# electric_scheme.net
KiCad netlist of a schematic drawn in EAGLE
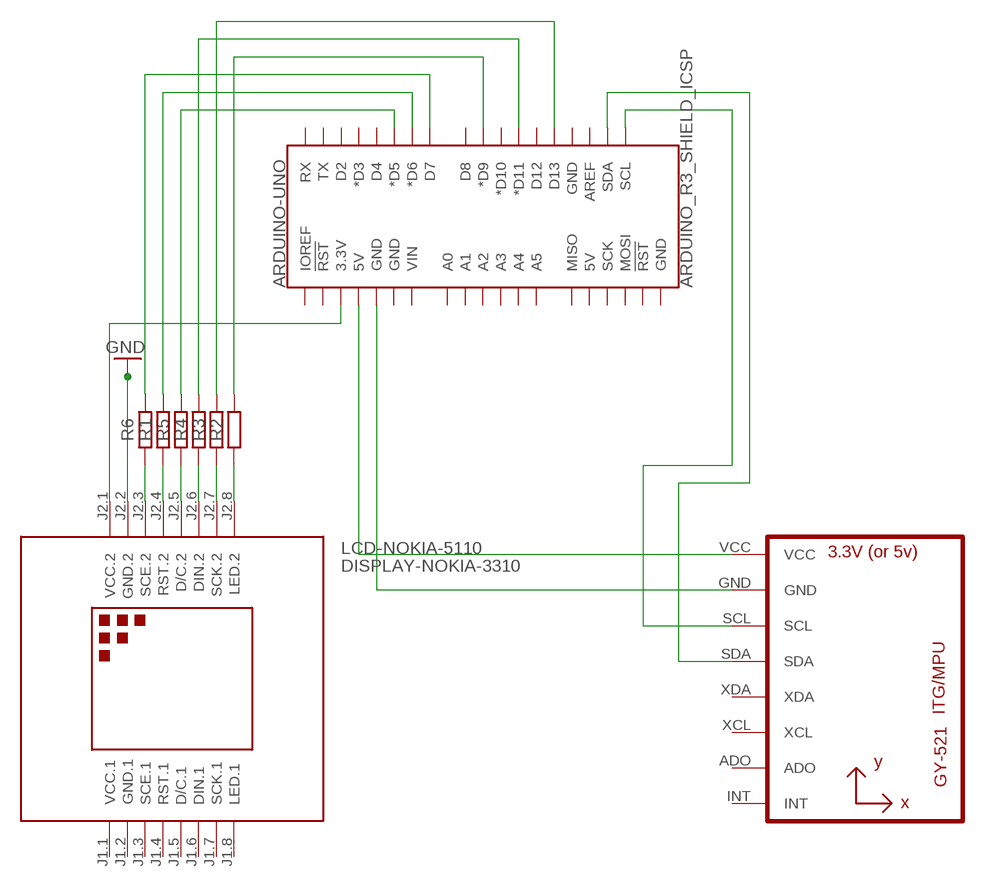
[diagram p0: schematic, sheet 1]

(export (version "E")
  (design (tool "Eeschema 10.0.6"))
  (components
    (comp (ref "ARDUINO-UNO")
      (value "ARDUINO_R3_SHIELD_ICSP")
      (footprint "eagle-import:UNO_R3_SHIELD_ICSP")
      (libsource (lib "eagle-import") (part "ARDUINO_R3_SHIELD_ICSP"))
    )
    (comp (ref "LCD-NOKIA-5110")
      (value "DISPLAY-NOKIA-3310")
      (footprint "eagle-import:DISPLAY-NOKIA-3310")
      (libsource (lib "eagle-import") (part "DISPLAY-NOKIA-3310"))
    )
    (comp (ref "MPU-6500")
      (value "GY-521MPU6050")
      (footprint "eagle-import:GY-521")
      (libsource (lib "eagle-import") (part "GY-521MPU6050"))
    )
    (comp (ref "R1")
      (value "R_AXIAL-11.7MM-PITCH")
      (footprint "eagle-import:RESAD1176W63L850D250B")
      (libsource (lib "eagle-import") (part "RAXIAL-11.7MM-PITCH_"))
    )
    (comp (ref "R2")
      (value "R_AXIAL-11.7MM-PITCH")
      (footprint "eagle-import:RESAD1176W63L850D250B")
      (libsource (lib "eagle-import") (part "RAXIAL-11.7MM-PITCH_"))
    )
    (comp (ref "R3")
      (value "R_AXIAL-11.7MM-PITCH")
      (footprint "eagle-import:RESAD1176W63L850D250B")
      (libsource (lib "eagle-import") (part "RAXIAL-11.7MM-PITCH_"))
    )
    (comp (ref "R4")
      (value "R_AXIAL-11.7MM-PITCH")
      (footprint "eagle-import:RESAD1176W63L850D250B")
      (libsource (lib "eagle-import") (part "RAXIAL-11.7MM-PITCH_"))
    )
    (comp (ref "R5")
      (value "R_AXIAL-11.7MM-PITCH")
      (footprint "eagle-import:RESAD1176W63L850D250B")
      (libsource (lib "eagle-import") (part "RAXIAL-11.7MM-PITCH_"))
    )
    (comp (ref "R6")
      (value "R_AXIAL-11.7MM-PITCH")
      (footprint "eagle-import:RESAD1176W63L850D250B")
      (libsource (lib "eagle-import") (part "RAXIAL-11.7MM-PITCH_"))
    )
  )
  (nets
    (net (code "1") (name "/GND.1") (class "Default")
      (node (ref "LCD-NOKIA-5110") (pin "J1.2") (pinfunction "GND.1_J1.2") (pintype "power_in"))
    )
    (net (code "2") (name "/VCC.1") (class "Default")
      (node (ref "LCD-NOKIA-5110") (pin "J1.1") (pinfunction "VCC.1_J1.1") (pintype "power_in"))
    )
    (net (code "3") (name "GND") (class "Default")
      (node (ref "LCD-NOKIA-5110") (pin "J2.2") (pinfunction "GND.2_J2.2") (pintype "power_in"))
    )
    (net (code "4") (name "Net-(ARDUINO-UNO-*D5)") (class "Default")
      (node (ref "ARDUINO-UNO") (pin "D5") (pinfunction "*D5_D5") (pintype "bidirectional"))
      (node (ref "R5") (pin "2") (pinfunction "2_2") (pintype "passive"))
    )
    (net (code "5") (name "Net-(ARDUINO-UNO-*D6)") (class "Default")
      (node (ref "ARDUINO-UNO") (pin "D6") (pinfunction "*D6_D6") (pintype "bidirectional"))
      (node (ref "R1") (pin "2") (pinfunction "2_2") (pintype "passive"))
    )
    (net (code "6") (name "Net-(ARDUINO-UNO-*D9)") (class "Default")
      (node (ref "ARDUINO-UNO") (pin "D9") (pinfunction "*D9_D9") (pintype "bidirectional"))
      (node (ref "R2") (pin "2") (pinfunction "2_2") (pintype "passive"))
    )
    (net (code "7") (name "Net-(ARDUINO-UNO-*D11)") (class "Default")
      (node (ref "ARDUINO-UNO") (pin "D11") (pinfunction "*D11_D11") (pintype "bidirectional"))
      (node (ref "R4") (pin "2") (pinfunction "2_2") (pintype "passive"))
    )
    (net (code "8") (name "Net-(ARDUINO-UNO-GND-PadGND@0)") (class "Default")
      (node (ref "ARDUINO-UNO") (pin "GND@0") (pinfunction "GND_GND@0") (pintype "bidirectional"))
      (node (ref "MPU-6500") (pin "GND") (pinfunction "GND_GND") (pintype "bidirectional"))
    )
    (net (code "9") (name "Net-(ARDUINO-UNO-Pad5V)") (class "Default")
      (node (ref "ARDUINO-UNO") (pin "5V") (pinfunction "5V_5V") (pintype "bidirectional"))
      (node (ref "MPU-6500") (pin "VCC") (pinfunction "VCC_VCC") (pintype "bidirectional"))
    )
    (net (code "10") (name "Net-(ARDUINO-UNO-PadD7)") (class "Default")
      (node (ref "ARDUINO-UNO") (pin "D7") (pinfunction "D7_D7") (pintype "bidirectional"))
      (node (ref "R6") (pin "2") (pinfunction "2_2") (pintype "passive"))
    )
    (net (code "11") (name "Net-(ARDUINO-UNO-PadD13)") (class "Default")
      (node (ref "ARDUINO-UNO") (pin "D13") (pinfunction "D13_D13") (pintype "bidirectional"))
      (node (ref "R3") (pin "2") (pinfunction "2_2") (pintype "passive"))
    )
    (net (code "12") (name "Net-(ARDUINO-UNO-PadSCL)") (class "Default")
      (node (ref "ARDUINO-UNO") (pin "SCL") (pinfunction "SCL_SCL") (pintype "bidirectional"))
      (node (ref "MPU-6500") (pin "SCL") (pinfunction "SCL_SCL") (pintype "bidirectional"))
    )
    (net (code "13") (name "Net-(ARDUINO-UNO-PadSDA)") (class "Default")
      (node (ref "ARDUINO-UNO") (pin "SDA") (pinfunction "SDA_SDA") (pintype "bidirectional"))
      (node (ref "MPU-6500") (pin "SDA") (pinfunction "SDA_SDA") (pintype "bidirectional"))
    )
    (net (code "14") (name "Net-(LCD-NOKIA-5110-DIN.2)") (class "Default")
      (node (ref "LCD-NOKIA-5110") (pin "J2.6") (pinfunction "DIN.2_J2.6") (pintype "bidirectional"))
      (node (ref "R4") (pin "1") (pinfunction "1_1") (pintype "passive"))
    )
    (net (code "15") (name "Net-(LCD-NOKIA-5110-D{slash}C.2)") (class "Default")
      (node (ref "LCD-NOKIA-5110") (pin "J2.5") (pinfunction "D/C.2_J2.5") (pintype "bidirectional"))
      (node (ref "R5") (pin "1") (pinfunction "1_1") (pintype "passive"))
    )
    (net (code "16") (name "Net-(LCD-NOKIA-5110-LED.2)") (class "Default")
      (node (ref "LCD-NOKIA-5110") (pin "J2.8") (pinfunction "LED.2_J2.8") (pintype "input"))
      (node (ref "R2") (pin "1") (pinfunction "1_1") (pintype "passive"))
    )
    (net (code "17") (name "Net-(LCD-NOKIA-5110-RST.2)") (class "Default")
      (node (ref "LCD-NOKIA-5110") (pin "J2.4") (pinfunction "RST.2_J2.4") (pintype "bidirectional"))
      (node (ref "R1") (pin "1") (pinfunction "1_1") (pintype "passive"))
    )
    (net (code "18") (name "Net-(LCD-NOKIA-5110-SCE.2)") (class "Default")
      (node (ref "LCD-NOKIA-5110") (pin "J2.3") (pinfunction "SCE.2_J2.3") (pintype "bidirectional"))
      (node (ref "R6") (pin "1") (pinfunction "1_1") (pintype "passive"))
    )
    (net (code "19") (name "Net-(LCD-NOKIA-5110-SCK.2)") (class "Default")
      (node (ref "LCD-NOKIA-5110") (pin "J2.7") (pinfunction "SCK.2_J2.7") (pintype "bidirectional"))
      (node (ref "R3") (pin "1") (pinfunction "1_1") (pintype "passive"))
    )
    (net (code "20") (name "Net-(LCD-NOKIA-5110-VCC.2)") (class "Default")
      (node (ref "ARDUINO-UNO") (pin "3.3V") (pinfunction "3.3V_3.3V") (pintype "bidirectional"))
      (node (ref "LCD-NOKIA-5110") (pin "J2.1") (pinfunction "VCC.2_J2.1") (pintype "power_in"))
    )
    (net (code "21") (name "unconnected-(ARDUINO-UNO-*D3-PadD3)") (class "Default")
      (node (ref "ARDUINO-UNO") (pin "D3") (pinfunction "*D3_D3") (pintype "bidirectional"))
    )
    (net (code "22") (name "unconnected-(ARDUINO-UNO-*D10-PadD10)") (class "Default")
      (node (ref "ARDUINO-UNO") (pin "D10") (pinfunction "*D10_D10") (pintype "bidirectional"))
    )
    (net (code "23") (name "unconnected-(ARDUINO-UNO-5V-Pad5V_ICSP)") (class "Default")
      (node (ref "ARDUINO-UNO") (pin "5V_ICSP") (pinfunction "5V_5V_ICSP") (pintype "bidirectional"))
    )
    (net (code "24") (name "unconnected-(ARDUINO-UNO-GND-PadGND@1)") (class "Default")
      (node (ref "ARDUINO-UNO") (pin "GND@1") (pinfunction "GND_GND@1") (pintype "bidirectional"))
    )
    (net (code "25") (name "unconnected-(ARDUINO-UNO-GND-PadGND@2)") (class "Default")
      (node (ref "ARDUINO-UNO") (pin "GND@2") (pinfunction "GND_GND@2") (pintype "bidirectional"))
    )
    (net (code "26") (name "unconnected-(ARDUINO-UNO-GND-PadGND_ICSP)") (class "Default")
      (node (ref "ARDUINO-UNO") (pin "GND_ICSP") (pinfunction "GND_GND_ICSP") (pintype "bidirectional"))
    )
    (net (code "27") (name "unconnected-(ARDUINO-UNO-PadA0)") (class "Default")
      (node (ref "ARDUINO-UNO") (pin "A0") (pinfunction "A0_A0") (pintype "bidirectional"))
    )
    (net (code "28") (name "unconnected-(ARDUINO-UNO-PadA1)") (class "Default")
      (node (ref "ARDUINO-UNO") (pin "A1") (pinfunction "A1_A1") (pintype "bidirectional"))
    )
    (net (code "29") (name "unconnected-(ARDUINO-UNO-PadA2)") (class "Default")
      (node (ref "ARDUINO-UNO") (pin "A2") (pinfunction "A2_A2") (pintype "bidirectional"))
    )
    (net (code "30") (name "unconnected-(ARDUINO-UNO-PadA3)") (class "Default")
      (node (ref "ARDUINO-UNO") (pin "A3") (pinfunction "A3_A3") (pintype "bidirectional"))
    )
    (net (code "31") (name "unconnected-(ARDUINO-UNO-PadA4)") (class "Default")
      (node (ref "ARDUINO-UNO") (pin "A4") (pinfunction "A4_A4") (pintype "bidirectional"))
    )
    (net (code "32") (name "unconnected-(ARDUINO-UNO-PadA5)") (class "Default")
      (node (ref "ARDUINO-UNO") (pin "A5") (pinfunction "A5_A5") (pintype "bidirectional"))
    )
    (net (code "33") (name "unconnected-(ARDUINO-UNO-PadAREF)") (class "Default")
      (node (ref "ARDUINO-UNO") (pin "AREF") (pinfunction "AREF_AREF") (pintype "bidirectional"))
    )
    (net (code "34") (name "unconnected-(ARDUINO-UNO-PadD2)") (class "Default")
      (node (ref "ARDUINO-UNO") (pin "D2") (pinfunction "D2_D2") (pintype "bidirectional"))
    )
    (net (code "35") (name "unconnected-(ARDUINO-UNO-PadD4)") (class "Default")
      (node (ref "ARDUINO-UNO") (pin "D4") (pinfunction "D4_D4") (pintype "bidirectional"))
    )
    (net (code "36") (name "unconnected-(ARDUINO-UNO-PadD8)") (class "Default")
      (node (ref "ARDUINO-UNO") (pin "D8") (pinfunction "D8_D8") (pintype "bidirectional"))
    )
    (net (code "37") (name "unconnected-(ARDUINO-UNO-PadD12)") (class "Default")
      (node (ref "ARDUINO-UNO") (pin "D12") (pinfunction "D12_D12") (pintype "bidirectional"))
    )
    (net (code "38") (name "unconnected-(ARDUINO-UNO-PadIOREF)") (class "Default")
      (node (ref "ARDUINO-UNO") (pin "IOREF") (pinfunction "IOREF_IOREF") (pintype "bidirectional"))
    )
    (net (code "39") (name "unconnected-(ARDUINO-UNO-PadMISO)") (class "Default")
      (node (ref "ARDUINO-UNO") (pin "MISO") (pinfunction "MISO_MISO") (pintype "bidirectional"))
    )
    (net (code "40") (name "unconnected-(ARDUINO-UNO-PadMOSI)") (class "Default")
      (node (ref "ARDUINO-UNO") (pin "MOSI") (pinfunction "MOSI_MOSI") (pintype "bidirectional"))
    )
    (net (code "41") (name "unconnected-(ARDUINO-UNO-PadRX)") (class "Default")
      (node (ref "ARDUINO-UNO") (pin "RX") (pinfunction "RX_RX") (pintype "bidirectional"))
    )
    (net (code "42") (name "unconnected-(ARDUINO-UNO-PadSCK)") (class "Default")
      (node (ref "ARDUINO-UNO") (pin "SCK") (pinfunction "SCK_SCK") (pintype "bidirectional"))
    )
    (net (code "43") (name "unconnected-(ARDUINO-UNO-PadTX)") (class "Default")
      (node (ref "ARDUINO-UNO") (pin "TX") (pinfunction "TX_TX") (pintype "bidirectional"))
    )
    (net (code "44") (name "unconnected-(ARDUINO-UNO-PadVIN)") (class "Default")
      (node (ref "ARDUINO-UNO") (pin "VIN") (pinfunction "VIN_VIN") (pintype "bidirectional"))
    )
    (net (code "45") (name "unconnected-(ARDUINO-UNO-~{RST}-PadRES)") (class "Default")
      (node (ref "ARDUINO-UNO") (pin "RES") (pinfunction "~{RST}_RES") (pintype "bidirectional"))
    )
    (net (code "46") (name "unconnected-(ARDUINO-UNO-~{RST}-PadRST_ICSP)") (class "Default")
      (node (ref "ARDUINO-UNO") (pin "RST_ICSP") (pinfunction "~{RST}_RST_ICSP") (pintype "bidirectional"))
    )
    (net (code "47") (name "unconnected-(LCD-NOKIA-5110-DIN.1-PadJ1.6)") (class "Default")
      (node (ref "LCD-NOKIA-5110") (pin "J1.6") (pinfunction "DIN.1_J1.6") (pintype "bidirectional"))
    )
    (net (code "48") (name "unconnected-(LCD-NOKIA-5110-D{slash}C.1-PadJ1.5)") (class "Default")
      (node (ref "LCD-NOKIA-5110") (pin "J1.5") (pinfunction "D/C.1_J1.5") (pintype "bidirectional"))
    )
    (net (code "49") (name "unconnected-(LCD-NOKIA-5110-LED.1-PadJ1.8)") (class "Default")
      (node (ref "LCD-NOKIA-5110") (pin "J1.8") (pinfunction "LED.1_J1.8") (pintype "input"))
    )
    (net (code "50") (name "unconnected-(LCD-NOKIA-5110-RST.1-PadJ1.4)") (class "Default")
      (node (ref "LCD-NOKIA-5110") (pin "J1.4") (pinfunction "RST.1_J1.4") (pintype "bidirectional"))
    )
    (net (code "51") (name "unconnected-(LCD-NOKIA-5110-SCE.1-PadJ1.3)") (class "Default")
      (node (ref "LCD-NOKIA-5110") (pin "J1.3") (pinfunction "SCE.1_J1.3") (pintype "bidirectional"))
    )
    (net (code "52") (name "unconnected-(LCD-NOKIA-5110-SCK.1-PadJ1.7)") (class "Default")
      (node (ref "LCD-NOKIA-5110") (pin "J1.7") (pinfunction "SCK.1_J1.7") (pintype "bidirectional"))
    )
    (net (code "53") (name "unconnected-(MPU-6500-PadADO)") (class "Default")
      (node (ref "MPU-6500") (pin "ADO") (pinfunction "ADO_ADO") (pintype "bidirectional"))
    )
    (net (code "54") (name "unconnected-(MPU-6500-PadINT)") (class "Default")
      (node (ref "MPU-6500") (pin "INT") (pinfunction "INT_INT") (pintype "bidirectional"))
    )
    (net (code "55") (name "unconnected-(MPU-6500-PadXCL)") (class "Default")
      (node (ref "MPU-6500") (pin "XCL") (pinfunction "XCL_XCL") (pintype "bidirectional"))
    )
    (net (code "56") (name "unconnected-(MPU-6500-PadXDA)") (class "Default")
      (node (ref "MPU-6500") (pin "XDA") (pinfunction "XDA_XDA") (pintype "bidirectional"))
    )
  )
)
